# REV0_3.net
KiCad netlist of a schematic drawn in Altium Designer
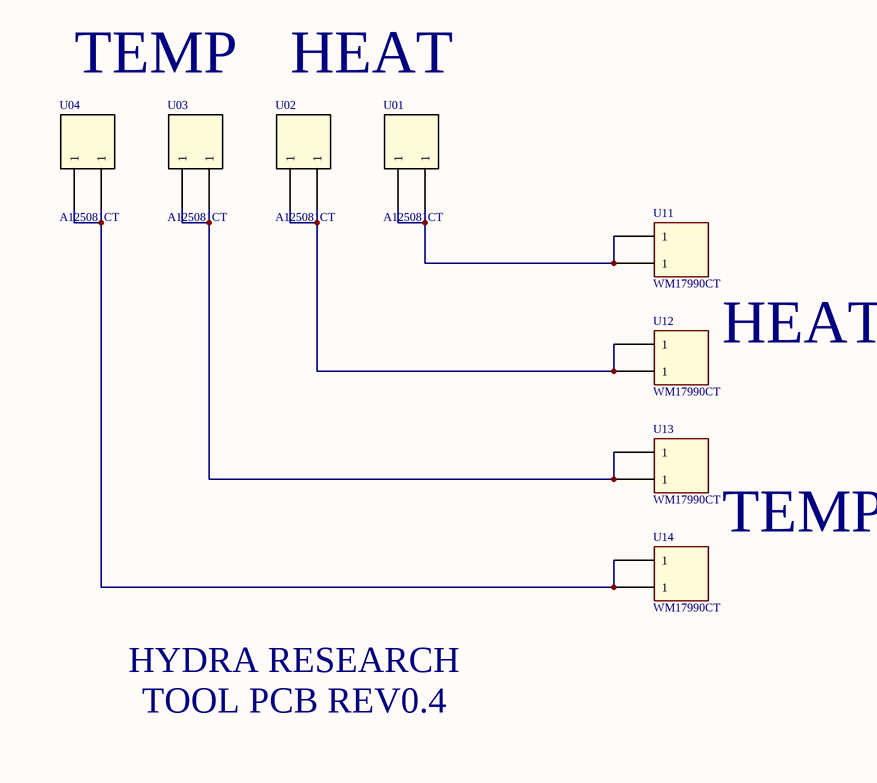
[diagram p0: REV0.3.SchDoc]

(export (version "E")
  (design (tool "Eeschema 10.0.6"))
  (components
    (comp (ref "U01")
      (value "A125081CT")
      (footprint "A125081CT-ND")
      (libsource (lib "Schlib1") (part "A125081CT"))
    )
    (comp (ref "U02")
      (value "A125081CT")
      (footprint "A125081CT-ND")
      (libsource (lib "Schlib1") (part "A125081CT"))
    )
    (comp (ref "U03")
      (value "A125081CT")
      (footprint "A125081CT-ND")
      (libsource (lib "Schlib1") (part "A125081CT"))
    )
    (comp (ref "U04")
      (value "A125081CT")
      (footprint "A125081CT-ND")
      (libsource (lib "Schlib1") (part "A125081CT"))
    )
    (comp (ref "U11")
      (value "WM17990CT")
      (footprint "WM17990CT-ND-l")
      (libsource (lib "Schlib1") (part "WM17990CT"))
    )
    (comp (ref "U12")
      (value "WM17990CT")
      (footprint "WM17990CT-ND-l")
      (libsource (lib "Schlib1") (part "WM17990CT"))
    )
    (comp (ref "U13")
      (value "WM17990CT")
      (footprint "WM17990CT-ND-l")
      (libsource (lib "Schlib1") (part "WM17990CT"))
    )
    (comp (ref "U14")
      (value "WM17990CT")
      (footprint "WM17990CT-ND-l")
      (libsource (lib "Schlib1") (part "WM17990CT"))
    )
  )
  (nets
    (net (code "1") (name "Net-(U01-Pad1)") (class "Default")
      (node (ref "U01") (pin "1") (pinfunction "1_1") (pintype "passive"))
      (node (ref "U11") (pin "1") (pinfunction "1_1") (pintype "passive"))
    )
    (net (code "2") (name "Net-(U02-Pad1)") (class "Default")
      (node (ref "U02") (pin "1") (pinfunction "1_1") (pintype "passive"))
      (node (ref "U12") (pin "1") (pinfunction "1_1") (pintype "passive"))
    )
    (net (code "3") (name "Net-(U03-Pad1)") (class "Default")
      (node (ref "U03") (pin "1") (pinfunction "1_1") (pintype "passive"))
      (node (ref "U13") (pin "1") (pinfunction "1_1") (pintype "passive"))
    )
    (net (code "4") (name "Net-(U04-Pad1)") (class "Default")
      (node (ref "U04") (pin "1") (pinfunction "1_1") (pintype "passive"))
      (node (ref "U14") (pin "1") (pinfunction "1_1") (pintype "passive"))
    )
  )
)
